# Board.net
KiCad netlist of a schematic drawn in EAGLE
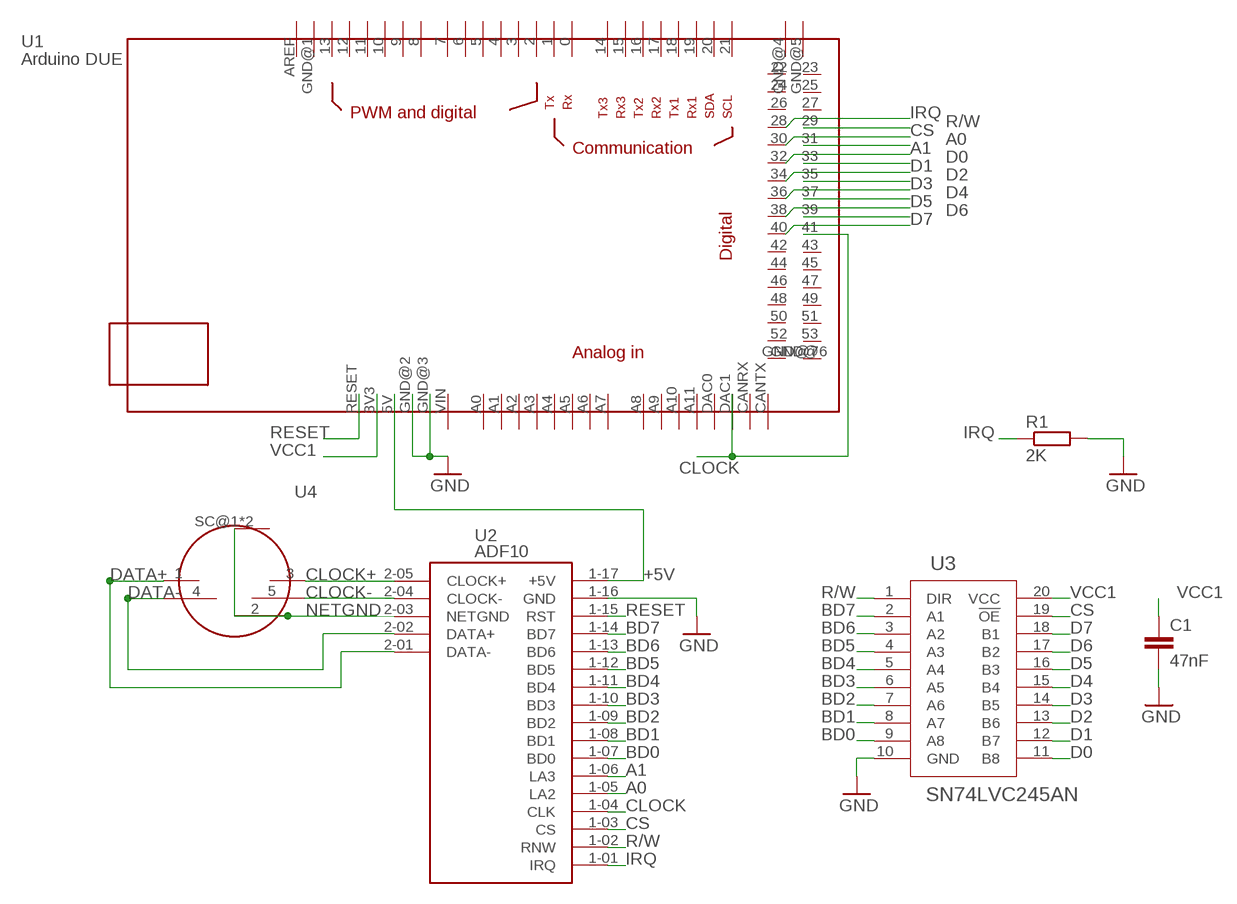
[diagram p0: schematic, sheet 1]

(export (version "E")
  (design (tool "Eeschema 10.0.6"))
  (components
    (comp (ref "C1")
      (value "47nF")
      (footprint "eagle-import:C050-035X075")
      (libsource (lib "eagle-import") (part "C-EU050-035X075"))
    )
    (comp (ref "R1")
      (value "2K")
      (footprint "eagle-import:0309_12")
      (libsource (lib "eagle-import") (part "R-EU_0309/12"))
    )
    (comp (ref "U1")
      (value "ARDUINODUE")
      (footprint "eagle-import:MEGABOX")
      (libsource (lib "eagle-import") (part "ARDUINODUE"))
    )
    (comp (ref "U2")
      (value "ADF10")
      (footprint "eagle-import:ADF10")
      (libsource (lib "eagle-import") (part "ADF10"))
    )
    (comp (ref "U3")
      (value "SN74LVC245AN")
      (footprint "eagle-import:N20")
      (libsource (lib "eagle-import") (part "SN74LVC245AN"))
    )
    (comp (ref "U4")
      (value "491087")
      (footprint "eagle-import:491087")
      (libsource (lib "eagle-import") (part "491087"))
    )
  )
  (nets
    (net (code "1") (name "/+5V") (class "Default")
      (node (ref "U1") (pin "5V") (pinfunction "5V_5V") (pintype "bidirectional"))
      (node (ref "U2") (pin "1-17") (pinfunction "+5V_1-17") (pintype "power_in"))
    )
    (net (code "2") (name "/A0") (class "Default")
      (node (ref "U1") (pin "31") (pinfunction "31_31") (pintype "bidirectional"))
      (node (ref "U2") (pin "1-05") (pinfunction "LA2_1-05") (pintype "input"))
    )
    (net (code "3") (name "/A1") (class "Default")
      (node (ref "U1") (pin "32") (pinfunction "32_32") (pintype "bidirectional"))
      (node (ref "U2") (pin "1-06") (pinfunction "LA3_1-06") (pintype "input"))
    )
    (net (code "4") (name "/BD0") (class "Default")
      (node (ref "U2") (pin "1-07") (pinfunction "BD0_1-07") (pintype "bidirectional"))
      (node (ref "U3") (pin "9") (pinfunction "A8_9") (pintype "bidirectional"))
    )
    (net (code "5") (name "/BD1") (class "Default")
      (node (ref "U2") (pin "1-08") (pinfunction "BD1_1-08") (pintype "bidirectional"))
      (node (ref "U3") (pin "8") (pinfunction "A7_8") (pintype "bidirectional"))
    )
    (net (code "6") (name "/BD2") (class "Default")
      (node (ref "U2") (pin "1-09") (pinfunction "BD2_1-09") (pintype "bidirectional"))
      (node (ref "U3") (pin "7") (pinfunction "A6_7") (pintype "bidirectional"))
    )
    (net (code "7") (name "/BD3") (class "Default")
      (node (ref "U2") (pin "1-10") (pinfunction "BD3_1-10") (pintype "bidirectional"))
      (node (ref "U3") (pin "6") (pinfunction "A5_6") (pintype "bidirectional"))
    )
    (net (code "8") (name "/BD4") (class "Default")
      (node (ref "U2") (pin "1-11") (pinfunction "BD4_1-11") (pintype "bidirectional"))
      (node (ref "U3") (pin "5") (pinfunction "A4_5") (pintype "bidirectional"))
    )
    (net (code "9") (name "/BD5") (class "Default")
      (node (ref "U2") (pin "1-12") (pinfunction "BD5_1-12") (pintype "bidirectional"))
      (node (ref "U3") (pin "4") (pinfunction "A3_4") (pintype "bidirectional"))
    )
    (net (code "10") (name "/BD6") (class "Default")
      (node (ref "U2") (pin "1-13") (pinfunction "BD6_1-13") (pintype "bidirectional"))
      (node (ref "U3") (pin "3") (pinfunction "A2_3") (pintype "bidirectional"))
    )
    (net (code "11") (name "/BD7") (class "Default")
      (node (ref "U2") (pin "1-14") (pinfunction "BD7_1-14") (pintype "bidirectional"))
      (node (ref "U3") (pin "2") (pinfunction "A1_2") (pintype "bidirectional"))
    )
    (net (code "12") (name "/CLOCK") (class "Default")
      (node (ref "U1") (pin "41") (pinfunction "41_41") (pintype "bidirectional"))
      (node (ref "U1") (pin "DAC1") (pinfunction "DAC1_DAC1") (pintype "bidirectional"))
      (node (ref "U2") (pin "1-04") (pinfunction "CLK_1-04") (pintype "input"))
    )
    (net (code "13") (name "/CLOCK+") (class "Default")
      (node (ref "U2") (pin "2-05") (pinfunction "CLOCK+_2-05") (pintype "bidirectional"))
      (node (ref "U4") (pin "3") (pinfunction "3_3") (pintype "bidirectional"))
    )
    (net (code "14") (name "/CLOCK-") (class "Default")
      (node (ref "U2") (pin "2-04") (pinfunction "CLOCK-_2-04") (pintype "bidirectional"))
      (node (ref "U4") (pin "5") (pinfunction "5_5") (pintype "bidirectional"))
    )
    (net (code "15") (name "/CS") (class "Default")
      (node (ref "U1") (pin "30") (pinfunction "30_30") (pintype "bidirectional"))
      (node (ref "U2") (pin "1-03") (pinfunction "CS_1-03") (pintype "input"))
      (node (ref "U3") (pin "19") (pinfunction "~{OE}_19") (pintype "input"))
    )
    (net (code "16") (name "/D0") (class "Default")
      (node (ref "U1") (pin "33") (pinfunction "33_33") (pintype "bidirectional"))
      (node (ref "U3") (pin "11") (pinfunction "B8_11") (pintype "bidirectional"))
    )
    (net (code "17") (name "/D1") (class "Default")
      (node (ref "U1") (pin "34") (pinfunction "34_34") (pintype "bidirectional"))
      (node (ref "U3") (pin "12") (pinfunction "B7_12") (pintype "bidirectional"))
    )
    (net (code "18") (name "/D2") (class "Default")
      (node (ref "U1") (pin "35") (pinfunction "35_35") (pintype "bidirectional"))
      (node (ref "U3") (pin "13") (pinfunction "B6_13") (pintype "bidirectional"))
    )
    (net (code "19") (name "/D3") (class "Default")
      (node (ref "U1") (pin "36") (pinfunction "36_36") (pintype "bidirectional"))
      (node (ref "U3") (pin "14") (pinfunction "B5_14") (pintype "bidirectional"))
    )
    (net (code "20") (name "/D4") (class "Default")
      (node (ref "U1") (pin "37") (pinfunction "37_37") (pintype "bidirectional"))
      (node (ref "U3") (pin "15") (pinfunction "B4_15") (pintype "bidirectional"))
    )
    (net (code "21") (name "/D5") (class "Default")
      (node (ref "U1") (pin "38") (pinfunction "38_38") (pintype "bidirectional"))
      (node (ref "U3") (pin "16") (pinfunction "B3_16") (pintype "bidirectional"))
    )
    (net (code "22") (name "/D6") (class "Default")
      (node (ref "U1") (pin "39") (pinfunction "39_39") (pintype "bidirectional"))
      (node (ref "U3") (pin "17") (pinfunction "B2_17") (pintype "bidirectional"))
    )
    (net (code "23") (name "/D7") (class "Default")
      (node (ref "U1") (pin "40") (pinfunction "40_40") (pintype "bidirectional"))
      (node (ref "U3") (pin "18") (pinfunction "B1_18") (pintype "bidirectional"))
    )
    (net (code "24") (name "/DATA+") (class "Default")
      (node (ref "U2") (pin "2-01") (pinfunction "DATA-_2-01") (pintype "bidirectional"))
      (node (ref "U4") (pin "1") (pinfunction "1_1") (pintype "bidirectional"))
    )
    (net (code "25") (name "/DATA-") (class "Default")
      (node (ref "U2") (pin "2-02") (pinfunction "DATA+_2-02") (pintype "bidirectional"))
      (node (ref "U4") (pin "4") (pinfunction "4_4") (pintype "bidirectional"))
    )
    (net (code "26") (name "/IRQ") (class "Default")
      (node (ref "R1") (pin "1") (pinfunction "1_1") (pintype "passive"))
      (node (ref "U1") (pin "28") (pinfunction "28_28") (pintype "bidirectional"))
      (node (ref "U2") (pin "1-01") (pinfunction "IRQ_1-01") (pintype "output"))
    )
    (net (code "27") (name "/NETGND") (class "Default")
      (node (ref "U2") (pin "2-03") (pinfunction "NETGND_2-03") (pintype "bidirectional"))
      (node (ref "U4") (pin "2") (pinfunction "2_2") (pintype "bidirectional"))
      (node (ref "U4") (pin "SC@1") (pinfunction "SHIELD_SC@1") (pintype "bidirectional"))
      (node (ref "U4") (pin "SC@2") (pinfunction "SHIELD_SC@2") (pintype "bidirectional"))
    )
    (net (code "28") (name "/RESET") (class "Default")
      (node (ref "U1") (pin "RESET") (pinfunction "RESET_RESET") (pintype "bidirectional"))
      (node (ref "U2") (pin "1-15") (pinfunction "RST_1-15") (pintype "input"))
    )
    (net (code "29") (name "/R{slash}W") (class "Default")
      (node (ref "U1") (pin "29") (pinfunction "29_29") (pintype "bidirectional"))
      (node (ref "U2") (pin "1-02") (pinfunction "RNW_1-02") (pintype "input"))
      (node (ref "U3") (pin "1") (pinfunction "DIR_1") (pintype "input"))
    )
    (net (code "30") (name "/VCC1") (class "Default")
      (node (ref "C1") (pin "1") (pinfunction "1_1") (pintype "passive"))
      (node (ref "U1") (pin "3V3") (pinfunction "3V3_3V3") (pintype "bidirectional"))
      (node (ref "U3") (pin "20") (pinfunction "VCC_20") (pintype "power_in"))
    )
    (net (code "31") (name "GND") (class "Default")
      (node (ref "C1") (pin "2") (pinfunction "2_2") (pintype "passive"))
      (node (ref "R1") (pin "2") (pinfunction "2_2") (pintype "passive"))
      (node (ref "U1") (pin "GND@2") (pinfunction "GND_GND@2") (pintype "bidirectional"))
      (node (ref "U1") (pin "GND@3") (pinfunction "GND_GND@3") (pintype "bidirectional"))
      (node (ref "U2") (pin "1-16") (pinfunction "GND_1-16") (pintype "power_in"))
      (node (ref "U3") (pin "10") (pinfunction "GND_10") (pintype "power_in"))
    )
    (net (code "32") (name "unconnected-(U1-GND-PadGND@1)") (class "Default")
      (node (ref "U1") (pin "GND@1") (pinfunction "GND_GND@1") (pintype "bidirectional"))
    )
    (net (code "33") (name "unconnected-(U1-GND-PadGND@4)") (class "Default")
      (node (ref "U1") (pin "GND@4") (pinfunction "GND_GND@4") (pintype "bidirectional"))
    )
    (net (code "34") (name "unconnected-(U1-GND-PadGND@5)") (class "Default")
      (node (ref "U1") (pin "GND@5") (pinfunction "GND_GND@5") (pintype "bidirectional"))
    )
    (net (code "35") (name "unconnected-(U1-GND-PadGND@6)") (class "Default")
      (node (ref "U1") (pin "GND@6") (pinfunction "GND_GND@6") (pintype "bidirectional"))
    )
    (net (code "36") (name "unconnected-(U1-GND-PadGND@7)") (class "Default")
      (node (ref "U1") (pin "GND@7") (pinfunction "GND_GND@7") (pintype "bidirectional"))
    )
    (net (code "37") (name "unconnected-(U1-Pad0)") (class "Default")
      (node (ref "U1") (pin "0") (pinfunction "0_0") (pintype "bidirectional"))
    )
    (net (code "38") (name "unconnected-(U1-Pad1)") (class "Default")
      (node (ref "U1") (pin "1") (pinfunction "1_1") (pintype "bidirectional"))
    )
    (net (code "39") (name "unconnected-(U1-Pad2)") (class "Default")
      (node (ref "U1") (pin "2") (pinfunction "2_2") (pintype "bidirectional"))
    )
    (net (code "40") (name "unconnected-(U1-Pad3)") (class "Default")
      (node (ref "U1") (pin "3") (pinfunction "3_3") (pintype "bidirectional"))
    )
    (net (code "41") (name "unconnected-(U1-Pad4)") (class "Default")
      (node (ref "U1") (pin "4") (pinfunction "4_4") (pintype "bidirectional"))
    )
    (net (code "42") (name "unconnected-(U1-Pad5)") (class "Default")
      (node (ref "U1") (pin "5") (pinfunction "5_5") (pintype "bidirectional"))
    )
    (net (code "43") (name "unconnected-(U1-Pad6)") (class "Default")
      (node (ref "U1") (pin "6") (pinfunction "6_6") (pintype "bidirectional"))
    )
    (net (code "44") (name "unconnected-(U1-Pad7)") (class "Default")
      (node (ref "U1") (pin "7") (pinfunction "7_7") (pintype "bidirectional"))
    )
    (net (code "45") (name "unconnected-(U1-Pad8)") (class "Default")
      (node (ref "U1") (pin "8") (pinfunction "8_8") (pintype "bidirectional"))
    )
    (net (code "46") (name "unconnected-(U1-Pad9)") (class "Default")
      (node (ref "U1") (pin "9") (pinfunction "9_9") (pintype "bidirectional"))
    )
    (net (code "47") (name "unconnected-(U1-Pad10)") (class "Default")
      (node (ref "U1") (pin "10") (pinfunction "10_10") (pintype "bidirectional"))
    )
    (net (code "48") (name "unconnected-(U1-Pad11)") (class "Default")
      (node (ref "U1") (pin "11") (pinfunction "11_11") (pintype "bidirectional"))
    )
    (net (code "49") (name "unconnected-(U1-Pad12)") (class "Default")
      (node (ref "U1") (pin "12") (pinfunction "12_12") (pintype "bidirectional"))
    )
    (net (code "50") (name "unconnected-(U1-Pad13)") (class "Default")
      (node (ref "U1") (pin "13") (pinfunction "13_13") (pintype "bidirectional"))
    )
    (net (code "51") (name "unconnected-(U1-Pad14)") (class "Default")
      (node (ref "U1") (pin "14") (pinfunction "14_14") (pintype "bidirectional"))
    )
    (net (code "52") (name "unconnected-(U1-Pad15)") (class "Default")
      (node (ref "U1") (pin "15") (pinfunction "15_15") (pintype "bidirectional"))
    )
    (net (code "53") (name "unconnected-(U1-Pad16)") (class "Default")
      (node (ref "U1") (pin "16") (pinfunction "16_16") (pintype "bidirectional"))
    )
    (net (code "54") (name "unconnected-(U1-Pad17)") (class "Default")
      (node (ref "U1") (pin "17") (pinfunction "17_17") (pintype "bidirectional"))
    )
    (net (code "55") (name "unconnected-(U1-Pad18)") (class "Default")
      (node (ref "U1") (pin "18") (pinfunction "18_18") (pintype "bidirectional"))
    )
    (net (code "56") (name "unconnected-(U1-Pad19)") (class "Default")
      (node (ref "U1") (pin "19") (pinfunction "19_19") (pintype "bidirectional"))
    )
    (net (code "57") (name "unconnected-(U1-Pad20)") (class "Default")
      (node (ref "U1") (pin "20") (pinfunction "20_20") (pintype "bidirectional"))
    )
    (net (code "58") (name "unconnected-(U1-Pad21)") (class "Default")
      (node (ref "U1") (pin "21") (pinfunction "21_21") (pintype "bidirectional"))
    )
    (net (code "59") (name "unconnected-(U1-Pad22)") (class "Default")
      (node (ref "U1") (pin "22") (pinfunction "22_22") (pintype "bidirectional"))
    )
    (net (code "60") (name "unconnected-(U1-Pad23)") (class "Default")
      (node (ref "U1") (pin "23") (pinfunction "23_23") (pintype "bidirectional"))
    )
    (net (code "61") (name "unconnected-(U1-Pad24)") (class "Default")
      (node (ref "U1") (pin "24") (pinfunction "24_24") (pintype "bidirectional"))
    )
    (net (code "62") (name "unconnected-(U1-Pad25)") (class "Default")
      (node (ref "U1") (pin "25") (pinfunction "25_25") (pintype "bidirectional"))
    )
    (net (code "63") (name "unconnected-(U1-Pad26)") (class "Default")
      (node (ref "U1") (pin "26") (pinfunction "26_26") (pintype "bidirectional"))
    )
    (net (code "64") (name "unconnected-(U1-Pad27)") (class "Default")
      (node (ref "U1") (pin "27") (pinfunction "27_27") (pintype "bidirectional"))
    )
    (net (code "65") (name "unconnected-(U1-Pad42)") (class "Default")
      (node (ref "U1") (pin "42") (pinfunction "42_42") (pintype "bidirectional"))
    )
    (net (code "66") (name "unconnected-(U1-Pad43)") (class "Default")
      (node (ref "U1") (pin "43") (pinfunction "43_43") (pintype "bidirectional"))
    )
    (net (code "67") (name "unconnected-(U1-Pad44)") (class "Default")
      (node (ref "U1") (pin "44") (pinfunction "44_44") (pintype "bidirectional"))
    )
    (net (code "68") (name "unconnected-(U1-Pad45)") (class "Default")
      (node (ref "U1") (pin "45") (pinfunction "45_45") (pintype "bidirectional"))
    )
    (net (code "69") (name "unconnected-(U1-Pad46)") (class "Default")
      (node (ref "U1") (pin "46") (pinfunction "46_46") (pintype "bidirectional"))
    )
    (net (code "70") (name "unconnected-(U1-Pad47)") (class "Default")
      (node (ref "U1") (pin "47") (pinfunction "47_47") (pintype "bidirectional"))
    )
    (net (code "71") (name "unconnected-(U1-Pad48)") (class "Default")
      (node (ref "U1") (pin "48") (pinfunction "48_48") (pintype "bidirectional"))
    )
    (net (code "72") (name "unconnected-(U1-Pad49)") (class "Default")
      (node (ref "U1") (pin "49") (pinfunction "49_49") (pintype "bidirectional"))
    )
    (net (code "73") (name "unconnected-(U1-Pad50)") (class "Default")
      (node (ref "U1") (pin "50") (pinfunction "50_50") (pintype "bidirectional"))
    )
    (net (code "74") (name "unconnected-(U1-Pad51)") (class "Default")
      (node (ref "U1") (pin "51") (pinfunction "51_51") (pintype "bidirectional"))
    )
    (net (code "75") (name "unconnected-(U1-Pad52)") (class "Default")
      (node (ref "U1") (pin "52") (pinfunction "52_52") (pintype "bidirectional"))
    )
    (net (code "76") (name "unconnected-(U1-Pad53)") (class "Default")
      (node (ref "U1") (pin "53") (pinfunction "53_53") (pintype "bidirectional"))
    )
    (net (code "77") (name "unconnected-(U1-PadA0)") (class "Default")
      (node (ref "U1") (pin "A0") (pinfunction "A0_A0") (pintype "bidirectional"))
    )
    (net (code "78") (name "unconnected-(U1-PadA1)") (class "Default")
      (node (ref "U1") (pin "A1") (pinfunction "A1_A1") (pintype "bidirectional"))
    )
    (net (code "79") (name "unconnected-(U1-PadA2)") (class "Default")
      (node (ref "U1") (pin "A2") (pinfunction "A2_A2") (pintype "bidirectional"))
    )
    (net (code "80") (name "unconnected-(U1-PadA3)") (class "Default")
      (node (ref "U1") (pin "A3") (pinfunction "A3_A3") (pintype "bidirectional"))
    )
    (net (code "81") (name "unconnected-(U1-PadA4)") (class "Default")
      (node (ref "U1") (pin "A4") (pinfunction "A4_A4") (pintype "bidirectional"))
    )
    (net (code "82") (name "unconnected-(U1-PadA5)") (class "Default")
      (node (ref "U1") (pin "A5") (pinfunction "A5_A5") (pintype "bidirectional"))
    )
    (net (code "83") (name "unconnected-(U1-PadA6)") (class "Default")
      (node (ref "U1") (pin "A6") (pinfunction "A6_A6") (pintype "bidirectional"))
    )
    (net (code "84") (name "unconnected-(U1-PadA7)") (class "Default")
      (node (ref "U1") (pin "A7") (pinfunction "A7_A7") (pintype "bidirectional"))
    )
    (net (code "85") (name "unconnected-(U1-PadA8)") (class "Default")
      (node (ref "U1") (pin "A8") (pinfunction "A8_A8") (pintype "bidirectional"))
    )
    (net (code "86") (name "unconnected-(U1-PadA9)") (class "Default")
      (node (ref "U1") (pin "A9") (pinfunction "A9_A9") (pintype "bidirectional"))
    )
    (net (code "87") (name "unconnected-(U1-PadA10)") (class "Default")
      (node (ref "U1") (pin "A10") (pinfunction "A10_A10") (pintype "bidirectional"))
    )
    (net (code "88") (name "unconnected-(U1-PadA11)") (class "Default")
      (node (ref "U1") (pin "A11") (pinfunction "A11_A11") (pintype "bidirectional"))
    )
    (net (code "89") (name "unconnected-(U1-PadAREF)") (class "Default")
      (node (ref "U1") (pin "AREF") (pinfunction "AREF_AREF") (pintype "bidirectional"))
    )
    (net (code "90") (name "unconnected-(U1-PadCANRX)") (class "Default")
      (node (ref "U1") (pin "CANRX") (pinfunction "CANRX_CANRX") (pintype "bidirectional"))
    )
    (net (code "91") (name "unconnected-(U1-PadCANTX)") (class "Default")
      (node (ref "U1") (pin "CANTX") (pinfunction "CANTX_CANTX") (pintype "bidirectional"))
    )
    (net (code "92") (name "unconnected-(U1-PadDAC0)") (class "Default")
      (node (ref "U1") (pin "DAC0") (pinfunction "DAC0_DAC0") (pintype "bidirectional"))
    )
    (net (code "93") (name "unconnected-(U1-PadVIN)") (class "Default")
      (node (ref "U1") (pin "VIN") (pinfunction "VIN_VIN") (pintype "bidirectional"))
    )
  )
)
